# ME433_HW4.net
KiCad netlist of a schematic drawn in EAGLE
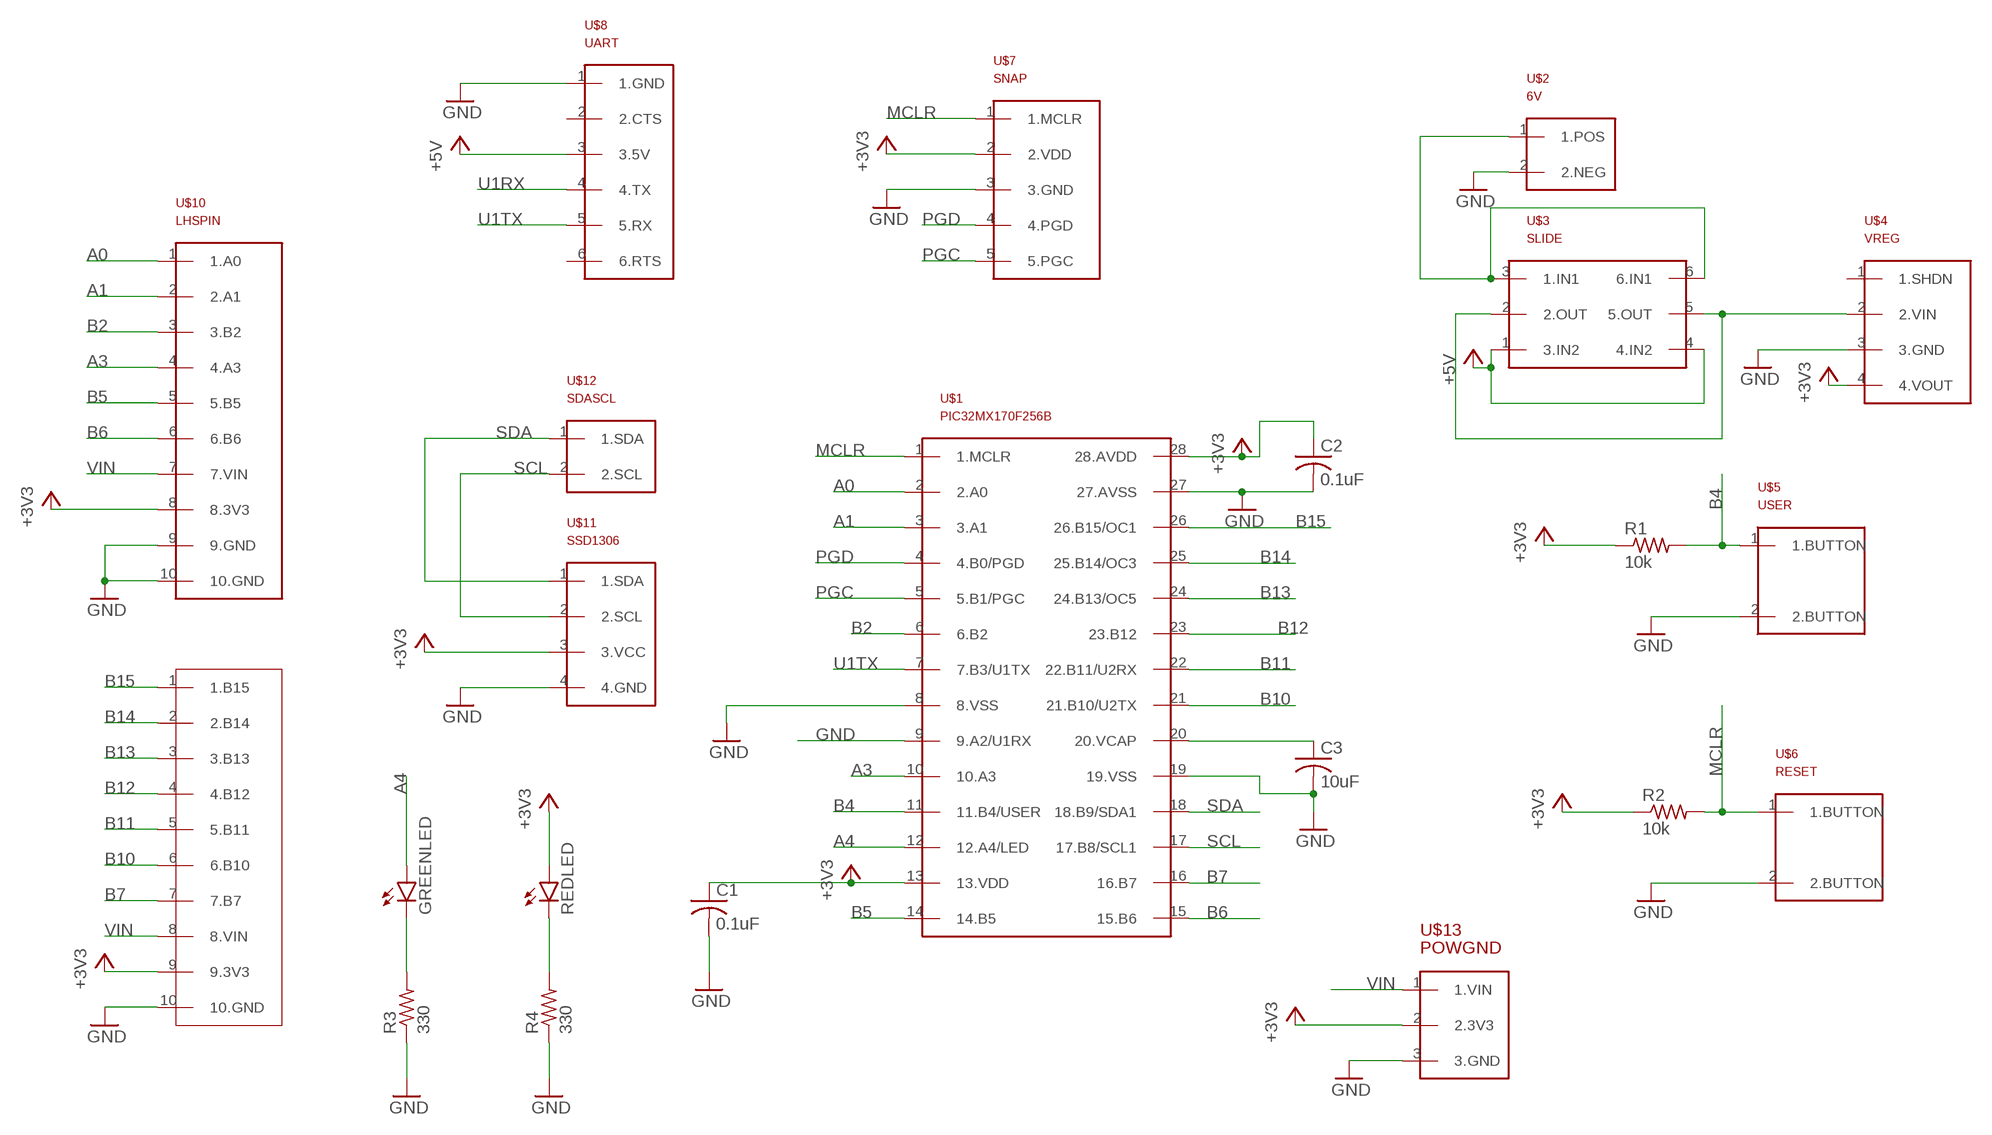
[diagram p0: schematic, sheet 1]

(export (version "E")
  (design (tool "Eeschema 10.0.6"))
  (components
    (comp (ref "C1")
      (value "0.1uF")
      (footprint "eagle-import:C025-030X050")
      (libsource (lib "eagle-import") (part "C-US025-030X050"))
    )
    (comp (ref "C2")
      (value "0.1uF")
      (footprint "eagle-import:C025-030X050")
      (libsource (lib "eagle-import") (part "C-US025-030X050"))
    )
    (comp (ref "C3")
      (value "10uF")
      (footprint "eagle-import:C025-030X050")
      (libsource (lib "eagle-import") (part "C-US025-030X050"))
    )
    (comp (ref "GREENLED")
      (value "LED3MM")
      (footprint "eagle-import:LED3MM")
      (libsource (lib "eagle-import") (part "LED3MM"))
    )
    (comp (ref "R1")
      (value "10k")
      (footprint "eagle-import:0207_10")
      (libsource (lib "eagle-import") (part "R-US_0207/10"))
    )
    (comp (ref "R2")
      (value "10k")
      (footprint "eagle-import:0207_10")
      (libsource (lib "eagle-import") (part "R-US_0207/10"))
    )
    (comp (ref "R3")
      (value "330")
      (footprint "eagle-import:0207_10")
      (libsource (lib "eagle-import") (part "R-US_0207/10"))
    )
    (comp (ref "R4")
      (value "330")
      (footprint "eagle-import:0207_10")
      (libsource (lib "eagle-import") (part "R-US_0207/10"))
    )
    (comp (ref "REDLED")
      (value "LED3MM")
      (footprint "eagle-import:LED3MM")
      (libsource (lib "eagle-import") (part "LED3MM"))
    )
    (comp (ref "U$1")
      (value "PIC32MX170F256B")
      (footprint "eagle-import:DIL28-3")
      (libsource (lib "eagle-import") (part "PIC32MX170F256B"))
    )
    (comp (ref "U$2") (value "6V") (footprint "eagle-import:6V") (libsource (lib "eagle-import") (part "6V")))
    (comp (ref "U$3")
      (value "SLIDE")
      (footprint "eagle-import:2X3")
      (libsource (lib "eagle-import") (part "SLIDE"))
    )
    (comp (ref "U$4")
      (value "VREG")
      (footprint "eagle-import:VREG")
      (libsource (lib "eagle-import") (part "VREG"))
    )
    (comp (ref "U$5")
      (value "USER")
      (footprint "eagle-import:BUTTON")
      (libsource (lib "eagle-import") (part "USER"))
    )
    (comp (ref "U$6")
      (value "RESET")
      (footprint "eagle-import:BUTTON")
      (libsource (lib "eagle-import") (part "RESET"))
    )
    (comp (ref "U$7")
      (value "SNAP")
      (footprint "eagle-import:1X05")
      (libsource (lib "eagle-import") (part "SNAP"))
    )
    (comp (ref "U$8")
      (value "UART")
      (footprint "eagle-import:UART")
      (libsource (lib "eagle-import") (part "UART"))
    )
    (comp (ref "U$9")
      (value "RHS_PIN")
      (footprint "eagle-import:RHSPIN")
      (libsource (lib "eagle-import") (part "RHS_PIN"))
    )
    (comp (ref "U$10")
      (value "LHSPIN")
      (footprint "eagle-import:LHSPIN")
      (libsource (lib "eagle-import") (part "LHSPIN"))
    )
    (comp (ref "U$11")
      (value "SSD1306")
      (footprint "eagle-import:SSD1306")
      (libsource (lib "eagle-import") (part "SSD1306"))
    )
    (comp (ref "U$12")
      (value "SDASCL")
      (footprint "eagle-import:SDASCL")
      (libsource (lib "eagle-import") (part "SDASCL"))
    )
    (comp (ref "U$13")
      (value "POWGND")
      (footprint "eagle-import:POWGND")
      (libsource (lib "eagle-import") (part "POWGND"))
    )
  )
  (nets
    (net (code "1") (name "+3V3") (class "Default")
      (node (ref "C1") (pin "1") (pinfunction "1_1") (pintype "passive"))
      (node (ref "C2") (pin "1") (pinfunction "1_1") (pintype "passive"))
      (node (ref "R1") (pin "1") (pinfunction "1_1") (pintype "passive"))
      (node (ref "R2") (pin "1") (pinfunction "1_1") (pintype "passive"))
      (node (ref "REDLED") (pin "A") (pinfunction "A_A") (pintype "passive"))
      (node (ref "U$1") (pin "13") (pinfunction "13.VDD_13") (pintype "bidirectional"))
      (node (ref "U$1") (pin "28") (pinfunction "28.AVDD_28") (pintype "bidirectional"))
      (node (ref "U$10") (pin "8") (pinfunction "8.3V3_8") (pintype "bidirectional"))
      (node (ref "U$11") (pin "3") (pinfunction "3.VCC_3") (pintype "bidirectional"))
      (node (ref "U$13") (pin "2") (pinfunction "2.3V3_2") (pintype "bidirectional"))
      (node (ref "U$4") (pin "4") (pinfunction "4.VOUT_4") (pintype "bidirectional"))
      (node (ref "U$7") (pin "2") (pinfunction "2.VDD_2") (pintype "bidirectional"))
      (node (ref "U$9") (pin "9") (pinfunction "9.3V3_9") (pintype "bidirectional"))
    )
    (net (code "2") (name "+5V") (class "Default")
      (node (ref "U$3") (pin "1") (pinfunction "3.IN2_1") (pintype "bidirectional"))
      (node (ref "U$3") (pin "4") (pinfunction "4.IN2_4") (pintype "bidirectional"))
      (node (ref "U$8") (pin "3") (pinfunction "3.5V_3") (pintype "bidirectional"))
    )
    (net (code "3") (name "/A0") (class "Default")
      (node (ref "U$1") (pin "2") (pinfunction "2.A0_2") (pintype "bidirectional"))
      (node (ref "U$10") (pin "1") (pinfunction "1.A0_1") (pintype "bidirectional"))
    )
    (net (code "4") (name "/A1") (class "Default")
      (node (ref "U$1") (pin "3") (pinfunction "3.A1_3") (pintype "bidirectional"))
      (node (ref "U$10") (pin "2") (pinfunction "2.A1_2") (pintype "bidirectional"))
    )
    (net (code "5") (name "/A3") (class "Default")
      (node (ref "U$1") (pin "10") (pinfunction "10.A3_10") (pintype "bidirectional"))
      (node (ref "U$10") (pin "4") (pinfunction "4.A3_4") (pintype "bidirectional"))
    )
    (net (code "6") (name "/A4") (class "Default")
      (node (ref "GREENLED") (pin "A") (pinfunction "A_A") (pintype "passive"))
      (node (ref "U$1") (pin "12") (pinfunction "12.A4/LED_12") (pintype "bidirectional"))
    )
    (net (code "7") (name "/B2") (class "Default")
      (node (ref "U$1") (pin "6") (pinfunction "6.B2_6") (pintype "bidirectional"))
      (node (ref "U$10") (pin "3") (pinfunction "3.B2_3") (pintype "bidirectional"))
    )
    (net (code "8") (name "/B4") (class "Default")
      (node (ref "R1") (pin "2") (pinfunction "2_2") (pintype "passive"))
      (node (ref "U$1") (pin "11") (pinfunction "11.B4/USER_11") (pintype "bidirectional"))
      (node (ref "U$5") (pin "1") (pinfunction "1.BUTTON_1") (pintype "bidirectional"))
    )
    (net (code "9") (name "/B5") (class "Default")
      (node (ref "U$1") (pin "14") (pinfunction "14.B5_14") (pintype "bidirectional"))
      (node (ref "U$10") (pin "5") (pinfunction "5.B5_5") (pintype "bidirectional"))
    )
    (net (code "10") (name "/B6") (class "Default")
      (node (ref "U$1") (pin "15") (pinfunction "15.B6_15") (pintype "bidirectional"))
      (node (ref "U$10") (pin "6") (pinfunction "6.B6_6") (pintype "bidirectional"))
    )
    (net (code "11") (name "/B7") (class "Default")
      (node (ref "U$1") (pin "16") (pinfunction "16.B7_16") (pintype "bidirectional"))
      (node (ref "U$9") (pin "7") (pinfunction "7.B7_7") (pintype "bidirectional"))
    )
    (net (code "12") (name "/B10") (class "Default")
      (node (ref "U$1") (pin "21") (pinfunction "21.B10/U2TX_21") (pintype "bidirectional"))
      (node (ref "U$9") (pin "6") (pinfunction "6.B10_6") (pintype "bidirectional"))
    )
    (net (code "13") (name "/B11") (class "Default")
      (node (ref "U$1") (pin "22") (pinfunction "22.B11/U2RX_22") (pintype "bidirectional"))
      (node (ref "U$9") (pin "5") (pinfunction "5.B11_5") (pintype "bidirectional"))
    )
    (net (code "14") (name "/B12") (class "Default")
      (node (ref "U$1") (pin "23") (pinfunction "23.B12_23") (pintype "bidirectional"))
      (node (ref "U$9") (pin "4") (pinfunction "4.B12_4") (pintype "bidirectional"))
    )
    (net (code "15") (name "/B13") (class "Default")
      (node (ref "U$1") (pin "24") (pinfunction "24.B13/OC5_24") (pintype "bidirectional"))
      (node (ref "U$9") (pin "3") (pinfunction "3.B13_3") (pintype "bidirectional"))
    )
    (net (code "16") (name "/B14") (class "Default")
      (node (ref "U$1") (pin "25") (pinfunction "25.B14/OC3_25") (pintype "bidirectional"))
      (node (ref "U$9") (pin "2") (pinfunction "2.B14_2") (pintype "bidirectional"))
    )
    (net (code "17") (name "/B15") (class "Default")
      (node (ref "U$1") (pin "26") (pinfunction "26.B15/OC1_26") (pintype "bidirectional"))
      (node (ref "U$9") (pin "1") (pinfunction "1.B15_1") (pintype "bidirectional"))
    )
    (net (code "18") (name "/MCLR") (class "Default")
      (node (ref "R2") (pin "2") (pinfunction "2_2") (pintype "passive"))
      (node (ref "U$1") (pin "1") (pinfunction "1.MCLR_1") (pintype "bidirectional"))
      (node (ref "U$6") (pin "1") (pinfunction "1.BUTTON_1") (pintype "bidirectional"))
      (node (ref "U$7") (pin "1") (pinfunction "1.MCLR_1") (pintype "bidirectional"))
    )
    (net (code "19") (name "/PGC") (class "Default")
      (node (ref "U$1") (pin "5") (pinfunction "5.B1/PGC_5") (pintype "bidirectional"))
      (node (ref "U$7") (pin "5") (pinfunction "5.PGC_5") (pintype "bidirectional"))
    )
    (net (code "20") (name "/PGD") (class "Default")
      (node (ref "U$1") (pin "4") (pinfunction "4.B0/PGD_4") (pintype "bidirectional"))
      (node (ref "U$7") (pin "4") (pinfunction "4.PGD_4") (pintype "bidirectional"))
    )
    (net (code "21") (name "/SCL") (class "Default")
      (node (ref "U$1") (pin "17") (pinfunction "17.B8/SCL1_17") (pintype "bidirectional"))
      (node (ref "U$11") (pin "2") (pinfunction "2.SCL_2") (pintype "bidirectional"))
      (node (ref "U$12") (pin "2") (pinfunction "2.SCL_2") (pintype "bidirectional"))
    )
    (net (code "22") (name "/SDA") (class "Default")
      (node (ref "U$1") (pin "18") (pinfunction "18.B9/SDA1_18") (pintype "bidirectional"))
      (node (ref "U$11") (pin "1") (pinfunction "1.SDA_1") (pintype "bidirectional"))
      (node (ref "U$12") (pin "1") (pinfunction "1.SDA_1") (pintype "bidirectional"))
    )
    (net (code "23") (name "/U1RX") (class "Default")
      (node (ref "U$1") (pin "9") (pinfunction "9.A2/U1RX_9") (pintype "bidirectional"))
      (node (ref "U$8") (pin "4") (pinfunction "4.TX_4") (pintype "bidirectional"))
    )
    (net (code "24") (name "/U1TX") (class "Default")
      (node (ref "U$1") (pin "7") (pinfunction "7.B3/U1TX_7") (pintype "bidirectional"))
      (node (ref "U$8") (pin "5") (pinfunction "5.RX_5") (pintype "bidirectional"))
    )
    (net (code "25") (name "/VIN") (class "Default")
      (node (ref "U$10") (pin "7") (pinfunction "7.VIN_7") (pintype "bidirectional"))
      (node (ref "U$13") (pin "1") (pinfunction "1.VIN_1") (pintype "bidirectional"))
      (node (ref "U$3") (pin "2") (pinfunction "2.OUT_2") (pintype "bidirectional"))
      (node (ref "U$3") (pin "5") (pinfunction "5.OUT_5") (pintype "bidirectional"))
      (node (ref "U$4") (pin "2") (pinfunction "2.VIN_2") (pintype "bidirectional"))
      (node (ref "U$9") (pin "8") (pinfunction "8.VIN_8") (pintype "bidirectional"))
    )
    (net (code "26") (name "GND") (class "Default")
      (node (ref "C1") (pin "2") (pinfunction "2_2") (pintype "passive"))
      (node (ref "C2") (pin "2") (pinfunction "2_2") (pintype "passive"))
      (node (ref "C3") (pin "2") (pinfunction "2_2") (pintype "passive"))
      (node (ref "R3") (pin "1") (pinfunction "1_1") (pintype "passive"))
      (node (ref "R4") (pin "1") (pinfunction "1_1") (pintype "passive"))
      (node (ref "U$1") (pin "19") (pinfunction "19.VSS_19") (pintype "bidirectional"))
      (node (ref "U$1") (pin "27") (pinfunction "27.AVSS_27") (pintype "bidirectional"))
      (node (ref "U$1") (pin "8") (pinfunction "8.VSS_8") (pintype "bidirectional"))
      (node (ref "U$10") (pin "10") (pinfunction "10.GND_10") (pintype "bidirectional"))
      (node (ref "U$10") (pin "9") (pinfunction "9.GND_9") (pintype "bidirectional"))
      (node (ref "U$11") (pin "4") (pinfunction "4.GND_4") (pintype "bidirectional"))
      (node (ref "U$13") (pin "3") (pinfunction "3.GND_3") (pintype "bidirectional"))
      (node (ref "U$2") (pin "2") (pinfunction "2.NEG_2") (pintype "bidirectional"))
      (node (ref "U$4") (pin "3") (pinfunction "3.GND_3") (pintype "bidirectional"))
      (node (ref "U$5") (pin "2") (pinfunction "2.BUTTON_2") (pintype "bidirectional"))
      (node (ref "U$6") (pin "2") (pinfunction "2.BUTTON_2") (pintype "bidirectional"))
      (node (ref "U$7") (pin "3") (pinfunction "3.GND_3") (pintype "bidirectional"))
      (node (ref "U$8") (pin "1") (pinfunction "1.GND_1") (pintype "bidirectional"))
      (node (ref "U$9") (pin "10") (pinfunction "10.GND_10") (pintype "bidirectional"))
    )
    (net (code "27") (name "Net-(GREENLED-C)") (class "Default")
      (node (ref "GREENLED") (pin "K") (pinfunction "C_K") (pintype "passive"))
      (node (ref "R3") (pin "2") (pinfunction "2_2") (pintype "passive"))
    )
    (net (code "28") (name "Net-(REDLED-C)") (class "Default")
      (node (ref "R4") (pin "2") (pinfunction "2_2") (pintype "passive"))
      (node (ref "REDLED") (pin "K") (pinfunction "C_K") (pintype "passive"))
    )
    (net (code "29") (name "Net-(U$1-20.VCAP)") (class "Default")
      (node (ref "C3") (pin "1") (pinfunction "1_1") (pintype "passive"))
      (node (ref "U$1") (pin "20") (pinfunction "20.VCAP_20") (pintype "bidirectional"))
    )
    (net (code "30") (name "Net-(U$2-1.POS)") (class "Default")
      (node (ref "U$2") (pin "1") (pinfunction "1.POS_1") (pintype "bidirectional"))
      (node (ref "U$3") (pin "3") (pinfunction "1.IN1_3") (pintype "bidirectional"))
      (node (ref "U$3") (pin "6") (pinfunction "6.IN1_6") (pintype "bidirectional"))
    )
    (net (code "31") (name "unconnected-(U$4-1.SHDN-Pad1)") (class "Default")
      (node (ref "U$4") (pin "1") (pinfunction "1.SHDN_1") (pintype "bidirectional"))
    )
    (net (code "32") (name "unconnected-(U$8-2.CTS-Pad2)") (class "Default")
      (node (ref "U$8") (pin "2") (pinfunction "2.CTS_2") (pintype "bidirectional"))
    )
    (net (code "33") (name "unconnected-(U$8-6.RTS-Pad6)") (class "Default")
      (node (ref "U$8") (pin "6") (pinfunction "6.RTS_6") (pintype "bidirectional"))
    )
  )
)
